# power_injector_small.net
KiCad netlist of a schematic drawn in EAGLE
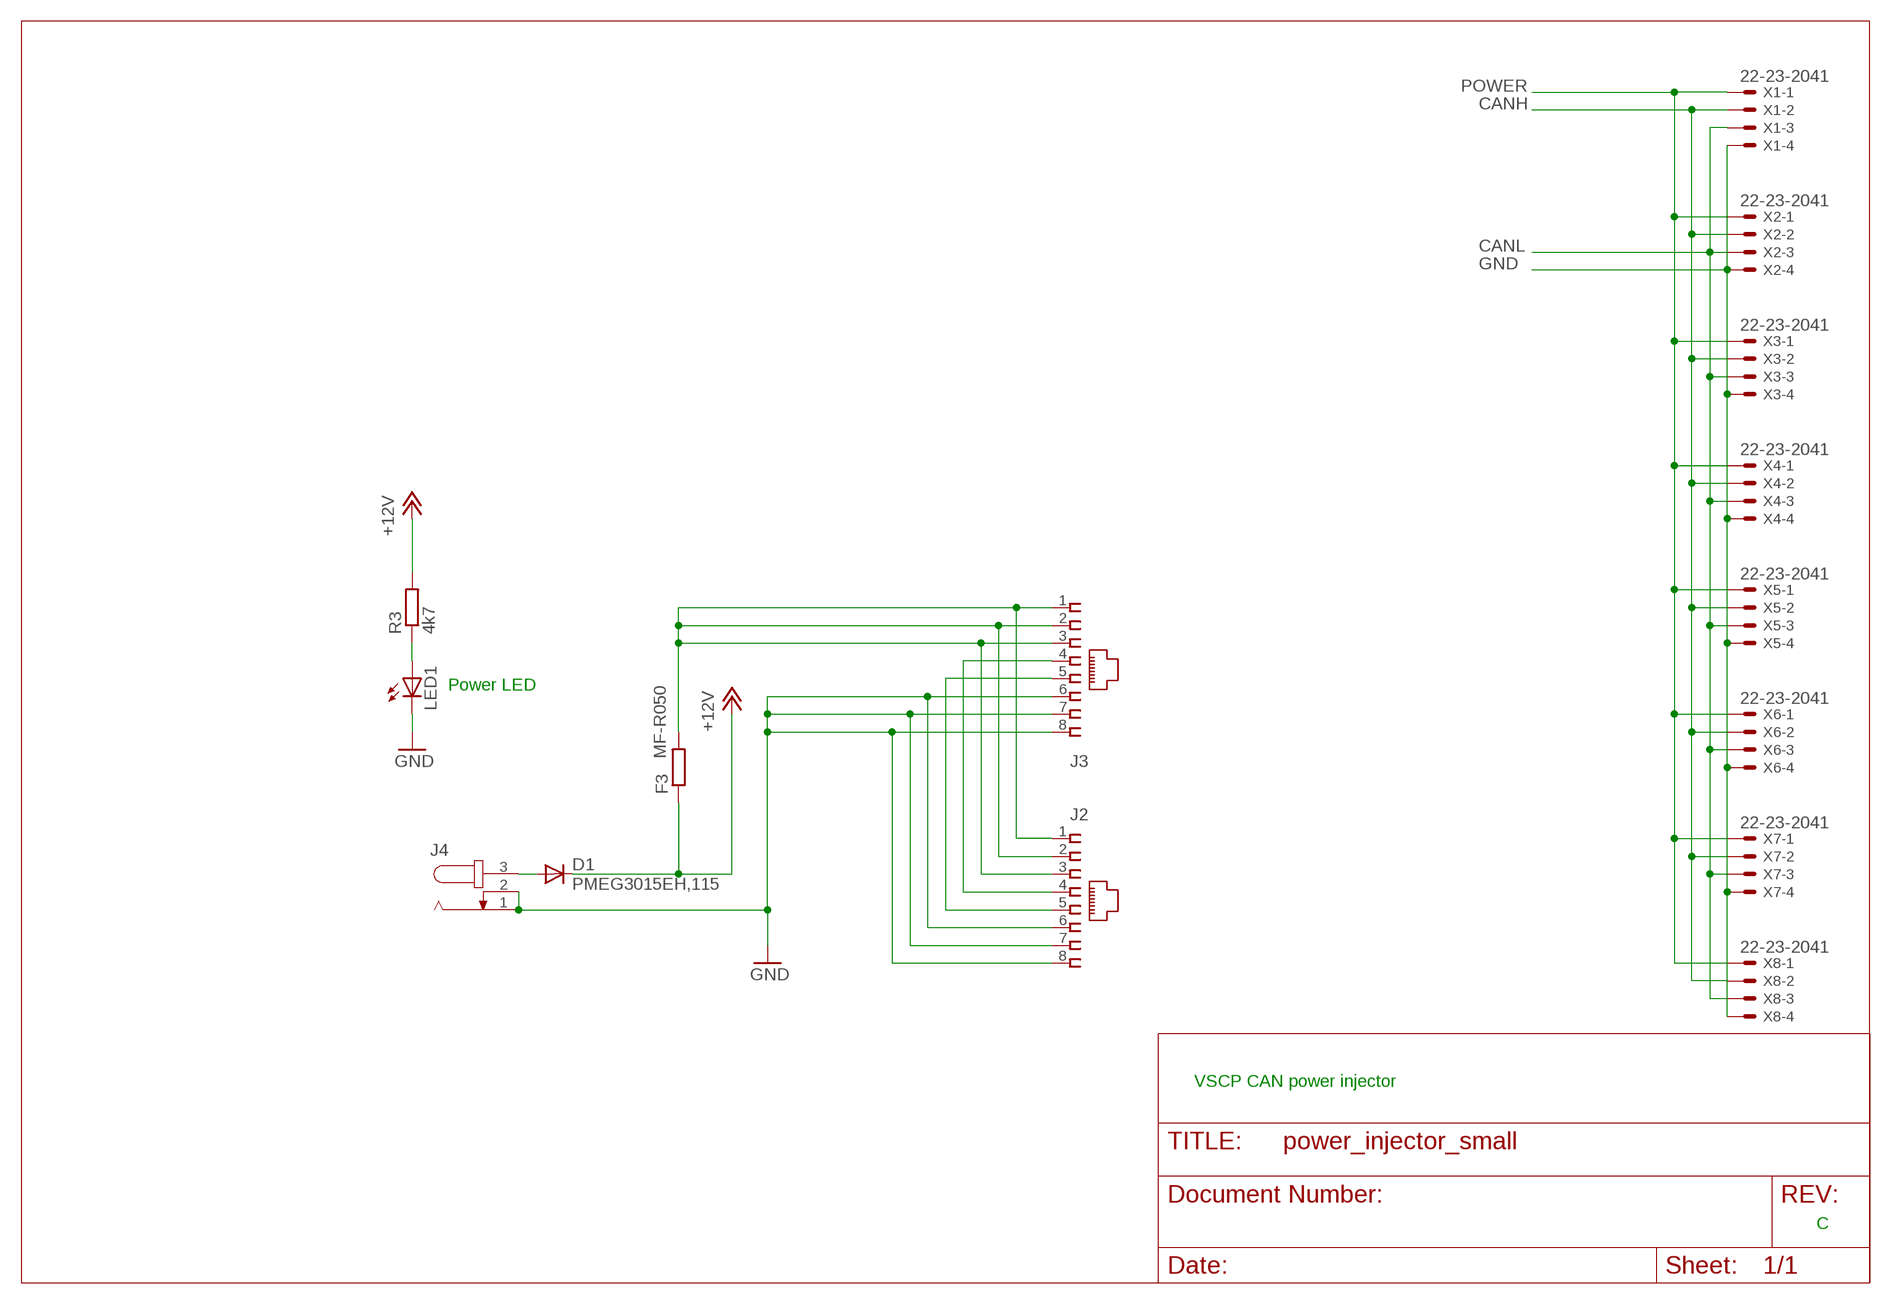
[diagram p0: schematic, sheet 1]

(export (version "E")
  (design (tool "Eeschema 10.0.6"))
  (components
    (comp (ref "D1")
      (value "PMEG3015EH,115")
      (footprint "eagle-import:SMB")
      (libsource (lib "eagle-import") (part "DIODE-SMB"))
    )
    (comp (ref "F3")
      (value "MF-R050")
      (footprint "eagle-import:0204_5")
      (libsource (lib "eagle-import") (part "R-EU_0204/5"))
    )
    (comp (ref "J2")
      (value "A00-108-220-450")
      (footprint "eagle-import:RJ-45")
      (libsource (lib "eagle-import") (part "A00-108-220-450"))
    )
    (comp (ref "J3")
      (value "A00-108-220-450")
      (footprint "eagle-import:RJ-45")
      (libsource (lib "eagle-import") (part "A00-108-220-450"))
    )
    (comp (ref "J4")
      (value "JACK-PLUG0")
      (footprint "eagle-import:SPC4077")
      (libsource (lib "eagle-import") (part "JACK-PLUG0"))
    )
    (comp (ref "LED1")
      (value "LEDCHIP-LED0805")
      (footprint "eagle-import:CHIP-LED0805")
      (libsource (lib "eagle-import") (part "LEDCHIP-LED0805"))
    )
    (comp (ref "R3")
      (value "4k7")
      (footprint "eagle-import:R0805")
      (libsource (lib "eagle-import") (part "R-EU_R0805"))
    )
    (comp (ref "X1")
      (value "22-23-2041")
      (footprint "eagle-import:22-23-2041")
      (fields (field (name "MF") "MOLEX"))
      (libsource (lib "eagle-import") (part "22-23-2041"))
    )
    (comp (ref "X2")
      (value "22-23-2041")
      (footprint "eagle-import:22-23-2041")
      (fields (field (name "MF") "MOLEX"))
      (libsource (lib "eagle-import") (part "22-23-2041"))
    )
    (comp (ref "X3")
      (value "22-23-2041")
      (footprint "eagle-import:22-23-2041")
      (fields (field (name "MF") "MOLEX"))
      (libsource (lib "eagle-import") (part "22-23-2041"))
    )
    (comp (ref "X4")
      (value "22-23-2041")
      (footprint "eagle-import:22-23-2041")
      (fields (field (name "MF") "MOLEX"))
      (libsource (lib "eagle-import") (part "22-23-2041"))
    )
    (comp (ref "X5")
      (value "22-23-2041")
      (footprint "eagle-import:22-23-2041")
      (fields (field (name "MF") "MOLEX"))
      (libsource (lib "eagle-import") (part "22-23-2041"))
    )
    (comp (ref "X6")
      (value "22-23-2041")
      (footprint "eagle-import:22-23-2041")
      (fields (field (name "MF") "MOLEX"))
      (libsource (lib "eagle-import") (part "22-23-2041"))
    )
    (comp (ref "X7")
      (value "22-23-2041")
      (footprint "eagle-import:22-23-2041")
      (fields (field (name "MF") "MOLEX"))
      (libsource (lib "eagle-import") (part "22-23-2041"))
    )
    (comp (ref "X8")
      (value "22-23-2041")
      (footprint "eagle-import:22-23-2041")
      (fields (field (name "MF") "MOLEX"))
      (libsource (lib "eagle-import") (part "22-23-2041"))
    )
  )
  (nets
    (net (code "1") (name "+12V") (class "Default")
      (node (ref "D1") (pin "C") (pinfunction "C_C") (pintype "passive"))
      (node (ref "F3") (pin "1") (pinfunction "1_1") (pintype "passive"))
      (node (ref "R3") (pin "2") (pinfunction "2_2") (pintype "passive"))
    )
    (net (code "2") (name "/CANH") (class "Default")
      (node (ref "J2") (pin "4") (pinfunction "4_4") (pintype "passive"))
      (node (ref "J3") (pin "4") (pinfunction "4_4") (pintype "passive"))
      (node (ref "X1") (pin "2") (pinfunction "S_2") (pintype "passive"))
      (node (ref "X2") (pin "2") (pinfunction "S_2") (pintype "passive"))
      (node (ref "X3") (pin "2") (pinfunction "S_2") (pintype "passive"))
      (node (ref "X4") (pin "2") (pinfunction "S_2") (pintype "passive"))
      (node (ref "X5") (pin "2") (pinfunction "S_2") (pintype "passive"))
      (node (ref "X6") (pin "2") (pinfunction "S_2") (pintype "passive"))
      (node (ref "X7") (pin "2") (pinfunction "S_2") (pintype "passive"))
      (node (ref "X8") (pin "2") (pinfunction "S_2") (pintype "passive"))
    )
    (net (code "3") (name "/CANL") (class "Default")
      (node (ref "J2") (pin "5") (pinfunction "5_5") (pintype "passive"))
      (node (ref "J3") (pin "5") (pinfunction "5_5") (pintype "passive"))
      (node (ref "X1") (pin "3") (pinfunction "S_3") (pintype "passive"))
      (node (ref "X2") (pin "3") (pinfunction "S_3") (pintype "passive"))
      (node (ref "X3") (pin "3") (pinfunction "S_3") (pintype "passive"))
      (node (ref "X4") (pin "3") (pinfunction "S_3") (pintype "passive"))
      (node (ref "X5") (pin "3") (pinfunction "S_3") (pintype "passive"))
      (node (ref "X6") (pin "3") (pinfunction "S_3") (pintype "passive"))
      (node (ref "X7") (pin "3") (pinfunction "S_3") (pintype "passive"))
      (node (ref "X8") (pin "3") (pinfunction "S_3") (pintype "passive"))
    )
    (net (code "4") (name "/POWER") (class "Default")
      (node (ref "F3") (pin "2") (pinfunction "2_2") (pintype "passive"))
      (node (ref "J2") (pin "1") (pinfunction "1_1") (pintype "passive"))
      (node (ref "J2") (pin "2") (pinfunction "2_2") (pintype "passive"))
      (node (ref "J2") (pin "3") (pinfunction "3_3") (pintype "passive"))
      (node (ref "J3") (pin "1") (pinfunction "1_1") (pintype "passive"))
      (node (ref "J3") (pin "2") (pinfunction "2_2") (pintype "passive"))
      (node (ref "J3") (pin "3") (pinfunction "3_3") (pintype "passive"))
      (node (ref "X1") (pin "1") (pinfunction "S_1") (pintype "passive"))
      (node (ref "X2") (pin "1") (pinfunction "S_1") (pintype "passive"))
      (node (ref "X3") (pin "1") (pinfunction "S_1") (pintype "passive"))
      (node (ref "X4") (pin "1") (pinfunction "S_1") (pintype "passive"))
      (node (ref "X5") (pin "1") (pinfunction "S_1") (pintype "passive"))
      (node (ref "X6") (pin "1") (pinfunction "S_1") (pintype "passive"))
      (node (ref "X7") (pin "1") (pinfunction "S_1") (pintype "passive"))
      (node (ref "X8") (pin "1") (pinfunction "S_1") (pintype "passive"))
    )
    (net (code "5") (name "GND") (class "Default")
      (node (ref "J2") (pin "6") (pinfunction "6_6") (pintype "passive"))
      (node (ref "J2") (pin "7") (pinfunction "7_7") (pintype "passive"))
      (node (ref "J2") (pin "8") (pinfunction "8_8") (pintype "passive"))
      (node (ref "J3") (pin "6") (pinfunction "6_6") (pintype "passive"))
      (node (ref "J3") (pin "7") (pinfunction "7_7") (pintype "passive"))
      (node (ref "J3") (pin "8") (pinfunction "8_8") (pintype "passive"))
      (node (ref "J4") (pin "1") (pinfunction "1_1") (pintype "passive"))
      (node (ref "J4") (pin "2") (pinfunction "2_2") (pintype "passive"))
      (node (ref "LED1") (pin "C") (pinfunction "C_C") (pintype "passive"))
      (node (ref "X1") (pin "4") (pinfunction "S_4") (pintype "passive"))
      (node (ref "X2") (pin "4") (pinfunction "S_4") (pintype "passive"))
      (node (ref "X3") (pin "4") (pinfunction "S_4") (pintype "passive"))
      (node (ref "X4") (pin "4") (pinfunction "S_4") (pintype "passive"))
      (node (ref "X5") (pin "4") (pinfunction "S_4") (pintype "passive"))
      (node (ref "X6") (pin "4") (pinfunction "S_4") (pintype "passive"))
      (node (ref "X7") (pin "4") (pinfunction "S_4") (pintype "passive"))
      (node (ref "X8") (pin "4") (pinfunction "S_4") (pintype "passive"))
    )
    (net (code "6") (name "Net-(D1-PadA)") (class "Default")
      (node (ref "D1") (pin "A") (pinfunction "A_A") (pintype "passive"))
      (node (ref "J4") (pin "3") (pinfunction "3_3") (pintype "passive"))
    )
    (net (code "7") (name "Net-(LED1-PadA)") (class "Default")
      (node (ref "LED1") (pin "A") (pinfunction "A_A") (pintype "passive"))
      (node (ref "R3") (pin "1") (pinfunction "1_1") (pintype "passive"))
    )
  )
)
